# SmartIMU_Dev_Sch.net
KiCad netlist of a schematic drawn in Altium Designer
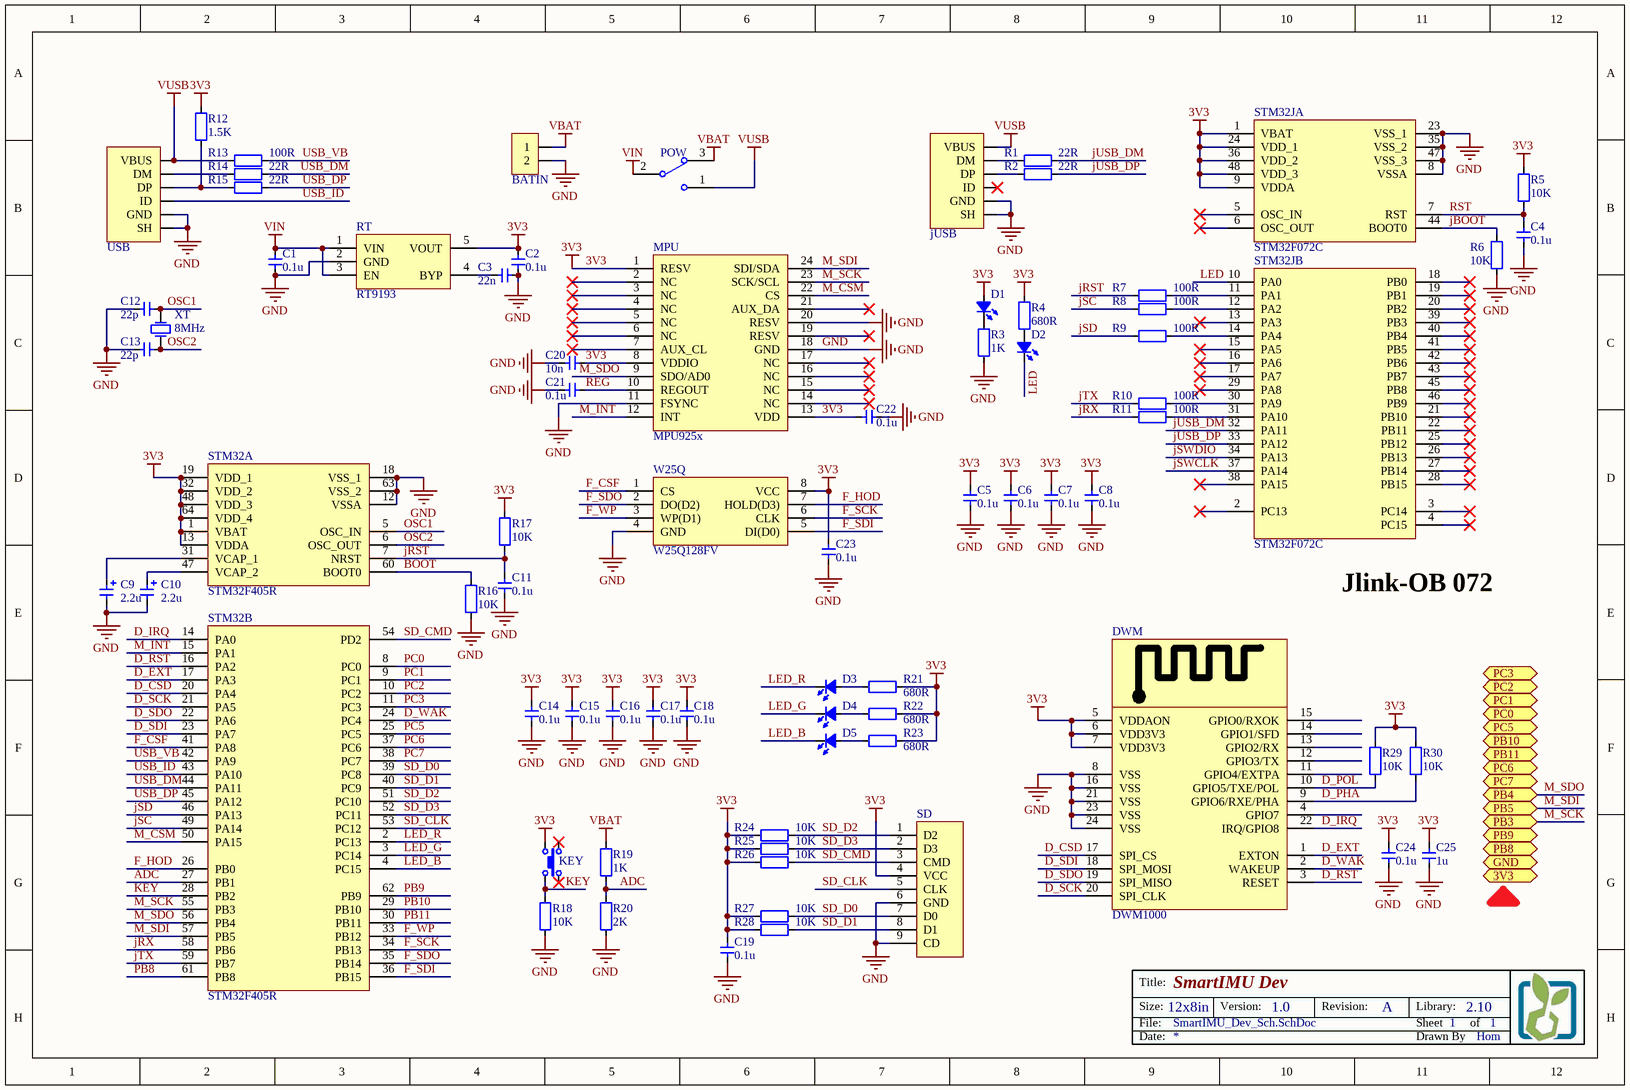
[diagram p0: SmartIMU_Dev_Sch.SchDoc]

(export (version "E")
  (design (tool "Eeschema 10.0.6"))
  (components
    (comp (ref "BATIN")
      (value "MX1.25_2P")
      (footprint "PCB_Connector:MX1.25_S90_2P")
      (description "MX")
      (libsource (lib "SCH_Connector") (part "MX1.25_2P"))
    )
    (comp (ref "C1")
      (value "0.1u")
      (footprint "PCB_PassiveCap:CAP_0603")
      (description "Capacitor")
      (fields (field (name "Comment") "Cap_0603"))
      (libsource (lib "SCH_Passive") (part "Cap_0603"))
    )
    (comp (ref "C2")
      (value "0.1u")
      (footprint "PCB_PassiveCap:CAP_0603")
      (description "Capacitor")
      (fields (field (name "Comment") "Cap_0603"))
      (libsource (lib "SCH_Passive") (part "Cap_0603"))
    )
    (comp (ref "C3")
      (value "22n")
      (footprint "PCB_PassiveCap:CAP_0603")
      (description "Capacitor")
      (fields (field (name "Comment") "Cap_0603"))
      (libsource (lib "SCH_Passive") (part "Cap_0603"))
    )
    (comp (ref "C4")
      (value "0.1u")
      (footprint "PCB_PassiveCap:CAP_0603")
      (description "Capacitor")
      (fields (field (name "Comment") "Cap_0603"))
      (libsource (lib "SCH_Passive") (part "Cap_0603"))
    )
    (comp (ref "C5")
      (value "0.1u")
      (footprint "PCB_PassiveCap:CAP_0603")
      (description "Capacitor")
      (fields (field (name "Comment") "Cap_0603"))
      (libsource (lib "SCH_Passive") (part "Cap_0603"))
    )
    (comp (ref "C6")
      (value "0.1u")
      (footprint "PCB_PassiveCap:CAP_0603")
      (description "Capacitor")
      (fields (field (name "Comment") "Cap_0603"))
      (libsource (lib "SCH_Passive") (part "Cap_0603"))
    )
    (comp (ref "C7")
      (value "0.1u")
      (footprint "PCB_PassiveCap:CAP_0603")
      (description "Capacitor")
      (fields (field (name "Comment") "Cap_0603"))
      (libsource (lib "SCH_Passive") (part "Cap_0603"))
    )
    (comp (ref "C8")
      (value "0.1u")
      (footprint "PCB_PassiveCap:CAP_0603")
      (description "Capacitor")
      (fields (field (name "Comment") "Cap_0603"))
      (libsource (lib "SCH_Passive") (part "Cap_0603"))
    )
    (comp (ref "C9")
      (value "2.2u")
      (footprint "PCB_PassiveCap:CAP_TAN_P0805")
      (description "Capacitor")
      (fields (field (name "Comment") "Cap_Tan_0805"))
      (libsource (lib "SCH_Passive") (part "Cap_Tan_0805"))
    )
    (comp (ref "C10")
      (value "2.2u")
      (footprint "PCB_PassiveCap:CAP_TAN_P0805")
      (description "Capacitor")
      (fields (field (name "Comment") "Cap_Tan_0805"))
      (libsource (lib "SCH_Passive") (part "Cap_Tan_0805"))
    )
    (comp (ref "C11")
      (value "0.1u")
      (footprint "PCB_PassiveCap:CAP_0603")
      (description "Capacitor")
      (fields (field (name "Comment") "Cap_0603"))
      (libsource (lib "SCH_Passive") (part "Cap_0603"))
    )
    (comp (ref "C12")
      (value "22p")
      (footprint "PCB_PassiveCap:CAP_0603")
      (description "Capacitor")
      (fields (field (name "Comment") "Cap_0603"))
      (libsource (lib "SCH_Passive") (part "Cap_0603"))
    )
    (comp (ref "C13")
      (value "22p")
      (footprint "PCB_PassiveCap:CAP_0603")
      (description "Capacitor")
      (fields (field (name "Comment") "Cap_0603"))
      (libsource (lib "SCH_Passive") (part "Cap_0603"))
    )
    (comp (ref "C14")
      (value "0.1u")
      (footprint "PCB_PassiveCap:CAP_0603")
      (description "Capacitor")
      (fields (field (name "Comment") "Cap_0603"))
      (libsource (lib "SCH_Passive") (part "Cap_0603"))
    )
    (comp (ref "C15")
      (value "0.1u")
      (footprint "PCB_PassiveCap:CAP_0603")
      (description "Capacitor")
      (fields (field (name "Comment") "Cap_0603"))
      (libsource (lib "SCH_Passive") (part "Cap_0603"))
    )
    (comp (ref "C16")
      (value "0.1u")
      (footprint "PCB_PassiveCap:CAP_0603")
      (description "Capacitor")
      (fields (field (name "Comment") "Cap_0603"))
      (libsource (lib "SCH_Passive") (part "Cap_0603"))
    )
    (comp (ref "C17")
      (value "0.1u")
      (footprint "PCB_PassiveCap:CAP_0603")
      (description "Capacitor")
      (fields (field (name "Comment") "Cap_0603"))
      (libsource (lib "SCH_Passive") (part "Cap_0603"))
    )
    (comp (ref "C18")
      (value "0.1u")
      (footprint "PCB_PassiveCap:CAP_0603")
      (description "Capacitor")
      (fields (field (name "Comment") "Cap_0603"))
      (libsource (lib "SCH_Passive") (part "Cap_0603"))
    )
    (comp (ref "C19")
      (value "0.1u")
      (footprint "PCB_PassiveCap:CAP_0603")
      (description "Capacitor")
      (fields (field (name "Comment") "Cap_0603"))
      (libsource (lib "SCH_Passive") (part "Cap_0603"))
    )
    (comp (ref "C20")
      (value "10n")
      (footprint "PCB_PassiveCap:CAP_0603")
      (description "Capacitor")
      (fields (field (name "Comment") "Cap_0603"))
      (libsource (lib "SCH_Passive") (part "Cap_0603"))
    )
    (comp (ref "C21")
      (value "0.1u")
      (footprint "PCB_PassiveCap:CAP_0603")
      (description "Capacitor")
      (fields (field (name "Comment") "Cap_0603"))
      (libsource (lib "SCH_Passive") (part "Cap_0603"))
    )
    (comp (ref "C22")
      (value "0.1u")
      (footprint "PCB_PassiveCap:CAP_0603")
      (description "Capacitor")
      (fields (field (name "Comment") "Cap_0603"))
      (libsource (lib "SCH_Passive") (part "Cap_0603"))
    )
    (comp (ref "C23")
      (value "0.1u")
      (footprint "PCB_PassiveCap:CAP_0603")
      (description "Capacitor")
      (fields (field (name "Comment") "Cap_0603"))
      (libsource (lib "SCH_Passive") (part "Cap_0603"))
    )
    (comp (ref "C24")
      (value "0.1u")
      (footprint "PCB_PassiveCap:CAP_0603")
      (description "Capacitor")
      (fields (field (name "Comment") "Cap_0603"))
      (libsource (lib "SCH_Passive") (part "Cap_0603"))
    )
    (comp (ref "C25")
      (value "1u")
      (footprint "PCB_PassiveCap:CAP_0603")
      (description "Capacitor")
      (fields (field (name "Comment") "Cap_0603"))
      (libsource (lib "SCH_Passive") (part "Cap_0603"))
    )
    (comp (ref "D1")
      (value "LED_0603")
      (footprint "PCB_ActiveLED:LED_0603_YELLOW")
      (description "LED")
      (libsource (lib "SCH_Active") (part "LED_0603"))
    )
    (comp (ref "D2")
      (value "LED_0603")
      (footprint "PCB_ActiveLED:LED_0603_ORANGE")
      (description "LED")
      (libsource (lib "SCH_Active") (part "LED_0603"))
    )
    (comp (ref "D3")
      (value "LED_0603")
      (footprint "PCB_ActiveLED:LED_0603_RED")
      (description "LED")
      (libsource (lib "SCH_Active") (part "LED_0603"))
    )
    (comp (ref "D4")
      (value "LED_0603")
      (footprint "PCB_ActiveLED:LED_0603_GREEN")
      (description "LED")
      (libsource (lib "SCH_Active") (part "LED_0603"))
    )
    (comp (ref "D5")
      (value "LED_0603")
      (footprint "PCB_ActiveLED:LED_0603_BLUE")
      (description "LED")
      (libsource (lib "SCH_Active") (part "LED_0603"))
    )
    (comp (ref "DWM")
      (value "DWM1000")
      (footprint "PCB_Module:DWM1000")
      (description "Module")
      (fields (field (name "MANUFACTURER") "Decawave Limited"))
      (libsource (lib "SCH_Module") (part "DWM1000"))
    )
    (comp (ref "jUSB")
      (value "USB_Micro")
      (footprint "PCB_USB:USB_Micro-AB")
      (description "USB")
      (libsource (lib "SCH_USB") (part "USB_Micro"))
    )
    (comp (ref "KEY")
      (value "ButtonTACT")
      (footprint "PCB_Switch:ButtonTACT_3.5*3.55_90")
      (description "Button")
      (libsource (lib "SCH_Switch") (part "ButtonTACT"))
    )
    (comp (ref "MPU")
      (value "MPU925x")
      (footprint "PCB_IntegratedCircuit:QFN_P0.4_24")
      (description "Sensor Motion")
      (libsource (lib "SCH_IntegratedCircuit") (part "MPU925x"))
    )
    (comp (ref "POW")
      (value "SwitchSPDT_2.8x6.6_90")
      (footprint "PCB_Switch:SwitchSPDT_2.8X6.6_90")
      (description "Switch")
      (libsource (lib "SCH_Switch") (part "SwitchSPDT_2.8x6.6_90"))
    )
    (comp (ref "R1")
      (value "22R")
      (footprint "PCB_PassiveRes:RES_0603")
      (description "Resistor")
      (fields (field (name "Comment") "Res_0603"))
      (libsource (lib "") (part "Res_0603_1"))
    )
    (comp (ref "R2")
      (value "22R")
      (footprint "PCB_PassiveRes:RES_0603")
      (description "Resistor")
      (fields (field (name "Comment") "Res_0603"))
      (libsource (lib "") (part "Res_0603_1"))
    )
    (comp (ref "R3")
      (value "1K")
      (footprint "PCB_PassiveRes:RES_0603")
      (description "Resistor")
      (fields (field (name "Comment") "Res_0603"))
      (libsource (lib "") (part "Res_0603_3"))
    )
    (comp (ref "R4")
      (value "680R")
      (footprint "PCB_PassiveRes:RES_0603")
      (description "Resistor")
      (fields (field (name "Comment") "Res_0603"))
      (libsource (lib "") (part "Res_0603_3"))
    )
    (comp (ref "R5")
      (value "10K")
      (footprint "PCB_PassiveRes:RES_0603")
      (description "Resistor")
      (fields (field (name "Comment") "Res_0603"))
      (libsource (lib "") (part "Res_0603_3"))
    )
    (comp (ref "R6")
      (value "10K")
      (footprint "PCB_PassiveRes:RES_0603")
      (description "Resistor")
      (fields (field (name "Comment") "Res_0603"))
      (libsource (lib "") (part "Res_0603_3"))
    )
    (comp (ref "R7")
      (value "100R")
      (footprint "PCB_PassiveRes:RES_0603")
      (description "Resistor")
      (fields (field (name "Comment") "Res_0603"))
      (libsource (lib "") (part "Res_0603_1"))
    )
    (comp (ref "R8")
      (value "100R")
      (footprint "PCB_PassiveRes:RES_0603")
      (description "Resistor")
      (fields (field (name "Comment") "Res_0603"))
      (libsource (lib "") (part "Res_0603_1"))
    )
    (comp (ref "R9")
      (value "100R")
      (footprint "PCB_PassiveRes:RES_0603")
      (description "Resistor")
      (fields (field (name "Comment") "Res_0603"))
      (libsource (lib "") (part "Res_0603_1"))
    )
    (comp (ref "R10")
      (value "100R")
      (footprint "PCB_PassiveRes:RES_0603")
      (description "Resistor")
      (fields (field (name "Comment") "Res_0603"))
      (libsource (lib "") (part "Res_0603_1"))
    )
    (comp (ref "R11")
      (value "100R")
      (footprint "PCB_PassiveRes:RES_0603")
      (description "Resistor")
      (fields (field (name "Comment") "Res_0603"))
      (libsource (lib "") (part "Res_0603_1"))
    )
    (comp (ref "R12")
      (value "1.5K")
      (footprint "PCB_PassiveRes:RES_0603")
      (description "Resistor")
      (fields (field (name "Comment") "Res_0603"))
      (libsource (lib "") (part "Res_0603_2"))
    )
    (comp (ref "R13")
      (value "100R")
      (footprint "PCB_PassiveRes:RES_0603")
      (description "Resistor")
      (fields (field (name "Comment") "Res_0603"))
      (libsource (lib "SCH_Passive") (part "Res_0603"))
    )
    (comp (ref "R14")
      (value "22R")
      (footprint "PCB_PassiveRes:RES_0603")
      (description "Resistor")
      (fields (field (name "Comment") "Res_0603"))
      (libsource (lib "SCH_Passive") (part "Res_0603"))
    )
    (comp (ref "R15")
      (value "22R")
      (footprint "PCB_PassiveRes:RES_0603")
      (description "Resistor")
      (fields (field (name "Comment") "Res_0603"))
      (libsource (lib "SCH_Passive") (part "Res_0603"))
    )
    (comp (ref "R16")
      (value "10K")
      (footprint "PCB_PassiveRes:RES_0603")
      (description "Resistor")
      (fields (field (name "Comment") "Res_0603"))
      (libsource (lib "") (part "Res_0603_3"))
    )
    (comp (ref "R17")
      (value "10K")
      (footprint "PCB_PassiveRes:RES_0603")
      (description "Resistor")
      (fields (field (name "Comment") "Res_0603"))
      (libsource (lib "") (part "Res_0603_3"))
    )
    (comp (ref "R18")
      (value "10K")
      (footprint "PCB_PassiveRes:RES_0603")
      (description "Resistor")
      (fields (field (name "Comment") "Res_0603"))
      (libsource (lib "") (part "Res_0603_3"))
    )
    (comp (ref "R19")
      (value "1K")
      (footprint "PCB_PassiveRes:RES_0603")
      (description "Resistor")
      (fields (field (name "Comment") "Res_0603"))
      (libsource (lib "") (part "Res_0603_2"))
    )
    (comp (ref "R20")
      (value "2K")
      (footprint "PCB_PassiveRes:RES_0603")
      (description "Resistor")
      (fields (field (name "Comment") "Res_0603"))
      (libsource (lib "") (part "Res_0603_2"))
    )
    (comp (ref "R21")
      (value "680R")
      (footprint "PCB_PassiveRes:RES_0603")
      (description "Resistor")
      (fields (field (name "Comment") "Res_0603"))
      (libsource (lib "SCH_Passive") (part "Res_0603"))
    )
    (comp (ref "R22")
      (value "680R")
      (footprint "PCB_PassiveRes:RES_0603")
      (description "Resistor")
      (fields (field (name "Comment") "Res_0603"))
      (libsource (lib "SCH_Passive") (part "Res_0603"))
    )
    (comp (ref "R23")
      (value "680R")
      (footprint "PCB_PassiveRes:RES_0603")
      (description "Resistor")
      (fields (field (name "Comment") "Res_0603"))
      (libsource (lib "SCH_Passive") (part "Res_0603"))
    )
    (comp (ref "R24")
      (value "10K")
      (footprint "PCB_PassiveRes:RES_0603")
      (description "Resistor")
      (fields (field (name "Comment") "Res_0603"))
      (libsource (lib "SCH_Passive") (part "Res_0603"))
    )
    (comp (ref "R25")
      (value "10K")
      (footprint "PCB_PassiveRes:RES_0603")
      (description "Resistor")
      (fields (field (name "Comment") "Res_0603"))
      (libsource (lib "SCH_Passive") (part "Res_0603"))
    )
    (comp (ref "R26")
      (value "10K")
      (footprint "PCB_PassiveRes:RES_0603")
      (description "Resistor")
      (fields (field (name "Comment") "Res_0603"))
      (libsource (lib "SCH_Passive") (part "Res_0603"))
    )
    (comp (ref "R27")
      (value "10K")
      (footprint "PCB_PassiveRes:RES_0603")
      (description "Resistor")
      (fields (field (name "Comment") "Res_0603"))
      (libsource (lib "SCH_Passive") (part "Res_0603"))
    )
    (comp (ref "R28")
      (value "10K")
      (footprint "PCB_PassiveRes:RES_0603")
      (description "Resistor")
      (fields (field (name "Comment") "Res_0603"))
      (libsource (lib "SCH_Passive") (part "Res_0603"))
    )
    (comp (ref "R29")
      (value "10K")
      (footprint "PCB_PassiveRes:RES_0603")
      (description "Resistor")
      (fields (field (name "Comment") "Res_0603"))
      (libsource (lib "") (part "Res_0603_3"))
    )
    (comp (ref "R30")
      (value "10K")
      (footprint "PCB_PassiveRes:RES_0603")
      (description "Resistor")
      (fields (field (name "Comment") "Res_0603"))
      (libsource (lib "") (part "Res_0603_3"))
    )
    (comp (ref "RT")
      (value "RT9193")
      (footprint "PCB_IntegratedCircuit:SOT23-5")
      (description "Power")
      (libsource (lib "SCH_IntegratedCircuit") (part "RT9193"))
    )
    (comp (ref "SD")
      (value "SD_Card_TF")
      (footprint "PCB_SDCard:SD_Card_TF")
      (description "SD")
      (libsource (lib "SCH_SDCard") (part "SD_Card_TF"))
    )
    (comp (ref "STM32")
      (value "STM32F405R")
      (footprint "PCB_IntegratedCircuit:LQFP_P0.5_64")
      (description "MCU")
      (libsource (lib "SCH_IntegratedCircuit") (part "STM32F405R"))
    )
    (comp (ref "STM32J")
      (value "STM32F072C")
      (footprint "PCB_IntegratedCircuit:LQFP_P0.5_48")
      (description "MCU")
      (libsource (lib "SCH_IntegratedCircuit") (part "STM32F103C"))
    )
    (comp (ref "USB")
      (value "USB_Micro")
      (footprint "PCB_USB:USB_Micro-AB")
      (description "USB")
      (libsource (lib "SCH_USB") (part "USB_Micro"))
    )
    (comp (ref "W25Q")
      (value "W25Q128FV")
      (footprint "PCB_IntegratedCircuit:SON_P1.27H_8")
      (description "FLASH")
      (libsource (lib "SCH_IntegratedCircuit") (part "W25Q_8"))
    )
    (comp (ref "XT")
      (value "8MHz")
      (footprint "PCB_Oscillator:XT_5032_2")
      (description "Crystal Oscillator")
      (fields (field (name "Comment") "XTAL_5032_2P"))
      (libsource (lib "SCH_Oscillator") (part "XTAL_5032_2P"))
    )
  )
  (nets
    (net (code "1") (name "/ADC") (class "Default")
      (node (ref "R19") (pin "2") (pinfunction "2_2") (pintype "passive"))
      (node (ref "R20") (pin "1") (pinfunction "1_1") (pintype "passive"))
      (node (ref "STM32") (pin "27") (pinfunction "PB1_27") (pintype "passive"))
    )
    (net (code "2") (name "/BOOT") (class "Default")
      (node (ref "R16") (pin "2") (pinfunction "2_2") (pintype "passive"))
      (node (ref "STM32") (pin "60") (pinfunction "BOOT0_60") (pintype "passive"))
    )
    (net (code "3") (name "/D_CSD") (class "Default")
      (node (ref "DWM") (pin "17") (pinfunction "SPI_CS_17") (pintype "passive"))
      (node (ref "STM32") (pin "20") (pinfunction "PA4_20") (pintype "passive"))
    )
    (net (code "4") (name "/D_EXT") (class "Default")
      (node (ref "DWM") (pin "1") (pinfunction "EXTON_1") (pintype "passive"))
      (node (ref "STM32") (pin "17") (pinfunction "PA3_17") (pintype "passive"))
    )
    (net (code "5") (name "/D_IRQ") (class "Default")
      (node (ref "DWM") (pin "22") (pinfunction "IRQ/GPIO8_22") (pintype "passive"))
      (node (ref "STM32") (pin "14") (pinfunction "PA0_14") (pintype "passive"))
    )
    (net (code "6") (name "/D_PHA") (class "Default")
      (node (ref "DWM") (pin "9") (pinfunction "GPIO6/RXE/PHA_9") (pintype "passive"))
      (node (ref "R30") (pin "1") (pinfunction "1_1") (pintype "passive"))
    )
    (net (code "7") (name "/D_POL") (class "Default")
      (node (ref "DWM") (pin "10") (pinfunction "GPIO5/TXE/POL_10") (pintype "passive"))
      (node (ref "R29") (pin "1") (pinfunction "1_1") (pintype "passive"))
    )
    (net (code "8") (name "/D_RST") (class "Default")
      (node (ref "DWM") (pin "3") (pinfunction "RESET_3") (pintype "passive"))
      (node (ref "STM32") (pin "16") (pinfunction "PA2_16") (pintype "passive"))
    )
    (net (code "9") (name "/D_SCK") (class "Default")
      (node (ref "DWM") (pin "20") (pinfunction "SPI_CLK_20") (pintype "passive"))
      (node (ref "STM32") (pin "21") (pinfunction "PA5_21") (pintype "passive"))
    )
    (net (code "10") (name "/D_SDI") (class "Default")
      (node (ref "DWM") (pin "18") (pinfunction "SPI_MOSI_18") (pintype "passive"))
      (node (ref "STM32") (pin "23") (pinfunction "PA7_23") (pintype "passive"))
    )
    (net (code "11") (name "/D_SDO") (class "Default")
      (node (ref "DWM") (pin "19") (pinfunction "SPI_MISO_19") (pintype "passive"))
      (node (ref "STM32") (pin "22") (pinfunction "PA6_22") (pintype "passive"))
    )
    (net (code "12") (name "/D_WAK") (class "Default")
      (node (ref "DWM") (pin "2") (pinfunction "WAKEUP_2") (pintype "passive"))
      (node (ref "STM32") (pin "24") (pinfunction "PC4_24") (pintype "passive"))
    )
    (net (code "13") (name "/F_CSF") (class "Default")
      (node (ref "STM32") (pin "41") (pinfunction "PA8_41") (pintype "passive"))
      (node (ref "W25Q") (pin "1") (pinfunction "CS_1") (pintype "passive"))
    )
    (net (code "14") (name "/F_HOD") (class "Default")
      (node (ref "STM32") (pin "26") (pinfunction "PB0_26") (pintype "passive"))
      (node (ref "W25Q") (pin "7") (pinfunction "HOLD(D3)_7") (pintype "passive"))
    )
    (net (code "15") (name "/F_SCK") (class "Default")
      (node (ref "STM32") (pin "34") (pinfunction "PB13_34") (pintype "passive"))
      (node (ref "W25Q") (pin "6") (pinfunction "CLK_6") (pintype "passive"))
    )
    (net (code "16") (name "/F_SDI") (class "Default")
      (node (ref "STM32") (pin "36") (pinfunction "PB15_36") (pintype "passive"))
      (node (ref "W25Q") (pin "5") (pinfunction "DI(D0)_5") (pintype "passive"))
    )
    (net (code "17") (name "/F_SDO") (class "Default")
      (node (ref "STM32") (pin "35") (pinfunction "PB14_35") (pintype "passive"))
      (node (ref "W25Q") (pin "2") (pinfunction "DO(D2)_2") (pintype "passive"))
    )
    (net (code "18") (name "/F_WP") (class "Default")
      (node (ref "STM32") (pin "33") (pinfunction "PB12_33") (pintype "passive"))
      (node (ref "W25Q") (pin "3") (pinfunction "WP(D1)_3") (pintype "passive"))
    )
    (net (code "19") (name "/KEY") (class "Default")
      (node (ref "KEY") (pin "1") (pinfunction "1_1") (pintype "passive"))
      (node (ref "R18") (pin "2") (pinfunction "2_2") (pintype "passive"))
      (node (ref "STM32") (pin "28") (pinfunction "PB2_28") (pintype "passive"))
    )
    (net (code "20") (name "/LED") (class "Default")
      (node (ref "D2") (pin "2") (pinfunction "K_2") (pintype "passive"))
      (node (ref "STM32J") (pin "10") (pinfunction "PA0_10") (pintype "passive"))
    )
    (net (code "21") (name "/LED_B") (class "Default")
      (node (ref "D5") (pin "2") (pinfunction "K_2") (pintype "passive"))
      (node (ref "STM32") (pin "4") (pinfunction "PC15_4") (pintype "passive"))
    )
    (net (code "22") (name "/LED_G") (class "Default")
      (node (ref "D4") (pin "2") (pinfunction "K_2") (pintype "passive"))
      (node (ref "STM32") (pin "3") (pinfunction "PC14_3") (pintype "passive"))
    )
    (net (code "23") (name "/LED_R") (class "Default")
      (node (ref "D3") (pin "2") (pinfunction "K_2") (pintype "passive"))
      (node (ref "STM32") (pin "2") (pinfunction "PC13_2") (pintype "passive"))
    )
    (net (code "24") (name "/M_CSM") (class "Default")
      (node (ref "MPU") (pin "22") (pinfunction "CS_22") (pintype "passive"))
      (node (ref "STM32") (pin "50") (pinfunction "PA15_50") (pintype "passive"))
    )
    (net (code "25") (name "/M_INT") (class "Default")
      (node (ref "MPU") (pin "12") (pinfunction "INT_12") (pintype "passive"))
      (node (ref "STM32") (pin "15") (pinfunction "PA1_15") (pintype "passive"))
    )
    (net (code "26") (name "/M_SCK") (class "Default")
      (node (ref "MPU") (pin "23") (pinfunction "SCK/SCL_23") (pintype "passive"))
      (node (ref "STM32") (pin "55") (pinfunction "PB3_55") (pintype "passive"))
    )
    (net (code "27") (name "/M_SDI") (class "Default")
      (node (ref "MPU") (pin "24") (pinfunction "SDI/SDA_24") (pintype "passive"))
      (node (ref "STM32") (pin "57") (pinfunction "PB5_57") (pintype "passive"))
    )
    (net (code "28") (name "/M_SDO") (class "Default")
      (node (ref "MPU") (pin "9") (pinfunction "SDO/AD0_9") (pintype "passive"))
      (node (ref "STM32") (pin "56") (pinfunction "PB4_56") (pintype "passive"))
    )
    (net (code "29") (name "/OSC1") (class "Default")
      (node (ref "C12") (pin "1") (pinfunction "1_1") (pintype "passive"))
      (node (ref "STM32") (pin "5") (pinfunction "OSC_IN_5") (pintype "passive"))
      (node (ref "XT") (pin "2") (pinfunction "OSC2_2") (pintype "passive"))
    )
    (net (code "30") (name "/OSC2") (class "Default")
      (node (ref "C13") (pin "1") (pinfunction "1_1") (pintype "passive"))
      (node (ref "STM32") (pin "6") (pinfunction "OSC_OUT_6") (pintype "passive"))
      (node (ref "XT") (pin "1") (pinfunction "OSC1_1") (pintype "passive"))
    )
    (net (code "31") (name "/PB8") (class "Default")
      (node (ref "STM32") (pin "61") (pinfunction "PB8_61") (pintype "passive"))
    )
    (net (code "32") (name "/PB9") (class "Default")
      (node (ref "STM32") (pin "62") (pinfunction "PB9_62") (pintype "passive"))
    )
    (net (code "33") (name "/PB10") (class "Default")
      (node (ref "STM32") (pin "29") (pinfunction "PB10_29") (pintype "passive"))
    )
    (net (code "34") (name "/PB11") (class "Default")
      (node (ref "STM32") (pin "30") (pinfunction "PB11_30") (pintype "passive"))
    )
    (net (code "35") (name "/PC0") (class "Default")
      (node (ref "STM32") (pin "8") (pinfunction "PC0_8") (pintype "passive"))
    )
    (net (code "36") (name "/PC1") (class "Default")
      (node (ref "STM32") (pin "9") (pinfunction "PC1_9") (pintype "passive"))
    )
    (net (code "37") (name "/PC2") (class "Default")
      (node (ref "STM32") (pin "10") (pinfunction "PC2_10") (pintype "passive"))
    )
    (net (code "38") (name "/PC3") (class "Default")
      (node (ref "STM32") (pin "11") (pinfunction "PC3_11") (pintype "passive"))
    )
    (net (code "39") (name "/PC5") (class "Default")
      (node (ref "STM32") (pin "25") (pinfunction "PC5_25") (pintype "passive"))
    )
    (net (code "40") (name "/PC6") (class "Default")
      (node (ref "STM32") (pin "37") (pinfunction "PC6_37") (pintype "passive"))
    )
    (net (code "41") (name "/PC7") (class "Default")
      (node (ref "STM32") (pin "38") (pinfunction "PC7_38") (pintype "passive"))
    )
    (net (code "42") (name "/REG") (class "Default")
      (node (ref "C21") (pin "2") (pinfunction "2_2") (pintype "passive"))
      (node (ref "MPU") (pin "10") (pinfunction "REGOUT_10") (pintype "passive"))
    )
    (net (code "43") (name "/RST") (class "Default")
      (node (ref "C4") (pin "2") (pinfunction "2_2") (pintype "passive"))
      (node (ref "R5") (pin "1") (pinfunction "1_1") (pintype "passive"))
      (node (ref "STM32J") (pin "7") (pinfunction "RST_7") (pintype "passive"))
    )
    (net (code "44") (name "/SD_CLK") (class "Default")
      (node (ref "SD") (pin "5") (pinfunction "CLK_5") (pintype "passive"))
      (node (ref "STM32") (pin "53") (pinfunction "PC12_53") (pintype "passive"))
    )
    (net (code "45") (name "/SD_CMD") (class "Default")
      (node (ref "R26") (pin "1") (pinfunction "1_1") (pintype "passive"))
      (node (ref "SD") (pin "3") (pinfunction "CMD_3") (pintype "passive"))
      (node (ref "STM32") (pin "54") (pinfunction "PD2_54") (pintype "passive"))
    )
    (net (code "46") (name "/SD_D0") (class "Default")
      (node (ref "R27") (pin "1") (pinfunction "1_1") (pintype "passive"))
      (node (ref "SD") (pin "7") (pinfunction "D0_7") (pintype "passive"))
      (node (ref "STM32") (pin "39") (pinfunction "PC8_39") (pintype "passive"))
    )
    (net (code "47") (name "/SD_D1") (class "Default")
      (node (ref "R28") (pin "1") (pinfunction "1_1") (pintype "passive"))
      (node (ref "SD") (pin "8") (pinfunction "D1_8") (pintype "passive"))
      (node (ref "STM32") (pin "40") (pinfunction "PC9_40") (pintype "passive"))
    )
    (net (code "48") (name "/SD_D2") (class "Default")
      (node (ref "R24") (pin "1") (pinfunction "1_1") (pintype "passive"))
      (node (ref "SD") (pin "1") (pinfunction "D2_1") (pintype "passive"))
      (node (ref "STM32") (pin "51") (pinfunction "PC10_51") (pintype "passive"))
    )
    (net (code "49") (name "/SD_D3") (class "Default")
      (node (ref "R25") (pin "1") (pinfunction "1_1") (pintype "passive"))
      (node (ref "SD") (pin "2") (pinfunction "D3_2") (pintype "passive"))
      (node (ref "STM32") (pin "52") (pinfunction "PC11_52") (pintype "passive"))
    )
    (net (code "50") (name "/USB_DM") (class "Default")
      (node (ref "R14") (pin "1") (pinfunction "1_1") (pintype "passive"))
      (node (ref "STM32") (pin "44") (pinfunction "PA11_44") (pintype "passive"))
    )
    (net (code "51") (name "/USB_DP") (class "Default")
      (node (ref "R15") (pin "1") (pinfunction "1_1") (pintype "passive"))
      (node (ref "STM32") (pin "45") (pinfunction "PA12_45") (pintype "passive"))
    )
    (net (code "52") (name "/USB_ID") (class "Default")
      (node (ref "STM32") (pin "43") (pinfunction "PA10_43") (pintype "passive"))
      (node (ref "USB") (pin "4") (pinfunction "ID_4") (pintype "passive"))
    )
    (net (code "53") (name "/USB_VB") (class "Default")
      (node (ref "R13") (pin "1") (pinfunction "1_1") (pintype "passive"))
      (node (ref "STM32") (pin "42") (pinfunction "PA9_42") (pintype "passive"))
    )
    (net (code "54") (name "/jBOOT") (class "Default")
      (node (ref "R6") (pin "2") (pinfunction "2_2") (pintype "passive"))
      (node (ref "STM32J") (pin "44") (pinfunction "BOOT0_44") (pintype "passive"))
    )
    (net (code "55") (name "/jRST") (class "Default")
      (node (ref "C11") (pin "2") (pinfunction "2_2") (pintype "passive"))
      (node (ref "R17") (pin "1") (pinfunction "1_1") (pintype "passive"))
      (node (ref "R7") (pin "1") (pinfunction "1_1") (pintype "passive"))
      (node (ref "STM32") (pin "7") (pinfunction "NRST_7") (pintype "passive"))
    )
    (net (code "56") (name "/jRX") (class "Default")
      (node (ref "R11") (pin "1") (pinfunction "1_1") (pintype "passive"))
      (node (ref "STM32") (pin "58") (pinfunction "PB6_58") (pintype "passive"))
    )
    (net (code "57") (name "/jSC") (class "Default")
      (node (ref "R8") (pin "1") (pinfunction "1_1") (pintype "passive"))
      (node (ref "STM32") (pin "49") (pinfunction "PA14_49") (pintype "passive"))
    )
    (net (code "58") (name "/jSD") (class "Default")
      (node (ref "R9") (pin "1") (pinfunction "1_1") (pintype "passive"))
      (node (ref "STM32") (pin "46") (pinfunction "PA13_46") (pintype "passive"))
    )
    (net (code "59") (name "/jSWCLK") (class "Default")
      (node (ref "STM32J") (pin "37") (pinfunction "PA14_37") (pintype "passive"))
    )
    (net (code "60") (name "/jSWDIO") (class "Default")
      (node (ref "STM32J") (pin "34") (pinfunction "PA13_34") (pintype "passive"))
    )
    (net (code "61") (name "/jTX") (class "Default")
      (node (ref "R10") (pin "1") (pinfunction "1_1") (pintype "passive"))
      (node (ref "STM32") (pin "59") (pinfunction "PB7_59") (pintype "passive"))
    )
    (net (code "62") (name "/jUSB_DM") (class "Default")
      (node (ref "R1") (pin "2") (pinfunction "2_2") (pintype "passive"))
      (node (ref "STM32J") (pin "32") (pinfunction "PA11_32") (pintype "passive"))
    )
    (net (code "63") (name "/jUSB_DP") (class "Default")
      (node (ref "R2") (pin "2") (pinfunction "2_2") (pintype "passive"))
      (node (ref "STM32J") (pin "33") (pinfunction "PA12_33") (pintype "passive"))
    )
    (net (code "64") (name "3V3") (class "Default")
      (node (ref "C14") (pin "1") (pinfunction "1_1") (pintype "passive"))
      (node (ref "C15") (pin "1") (pinfunction "1_1") (pintype "passive"))
      (node (ref "C16") (pin "1") (pinfunction "1_1") (pintype "passive"))
      (node (ref "C17") (pin "1") (pinfunction "1_1") (pintype "passive"))
      (node (ref "C18") (pin "2") (pinfunction "2_2") (pintype "passive"))
      (node (ref "C19") (pin "1") (pinfunction "1_1") (pintype "passive"))
      (node (ref "C2") (pin "2") (pinfunction "2_2") (pintype "passive"))
      (node (ref "C20") (pin "2") (pinfunction "2_2") (pintype "passive"))
      (node (ref "C22") (pin "2") (pinfunction "2_2") (pintype "passive"))
      (node (ref "C23") (pin "1") (pinfunction "1_1") (pintype "passive"))
      (node (ref "C24") (pin "1") (pinfunction "1_1") (pintype "passive"))
      (node (ref "C25") (pin "1") (pinfunction "1_1") (pintype "passive"))
      (node (ref "C5") (pin "2") (pinfunction "2_2") (pintype "passive"))
      (node (ref "C6") (pin "2") (pinfunction "2_2") (pintype "passive"))
      (node (ref "C7") (pin "2") (pinfunction "2_2") (pintype "passive"))
      (node (ref "C8") (pin "2") (pinfunction "2_2") (pintype "passive"))
      (node (ref "D1") (pin "1") (pinfunction "A_1") (pintype "passive"))
      (node (ref "DWM") (pin "5") (pinfunction "VDDAON_5") (pintype "passive"))
      (node (ref "DWM") (pin "6") (pinfunction "VDD3V3_6") (pintype "passive"))
      (node (ref "DWM") (pin "7") (pinfunction "VDD3V3_7") (pintype "passive"))
      (node (ref "KEY") (pin "2") (pinfunction "2_2") (pintype "passive"))
      (node (ref "MPU") (pin "1") (pinfunction "RESV_1") (pintype "passive"))
      (node (ref "MPU") (pin "13") (pinfunction "VDD_13") (pintype "passive"))
      (node (ref "MPU") (pin "8") (pinfunction "VDDIO_8") (pintype "passive"))
      (node (ref "R12") (pin "1") (pinfunction "1_1") (pintype "passive"))
      (node (ref "R17") (pin "2") (pinfunction "2_2") (pintype "passive"))
      (node (ref "R21") (pin "1") (pinfunction "1_1") (pintype "passive"))
      (node (ref "R22") (pin "1") (pinfunction "1_1") (pintype "passive"))
      (node (ref "R23") (pin "1") (pinfunction "1_1") (pintype "passive"))
      (node (ref "R24") (pin "2") (pinfunction "2_2") (pintype "passive"))
      (node (ref "R25") (pin "2") (pinfunction "2_2") (pintype "passive"))
      (node (ref "R26") (pin "2") (pinfunction "2_2") (pintype "passive"))
      (node (ref "R27") (pin "2") (pinfunction "2_2") (pintype "passive"))
      (node (ref "R28") (pin "2") (pinfunction "2_2") (pintype "passive"))
      (node (ref "R29") (pin "2") (pinfunction "2_2") (pintype "passive"))
      (node (ref "R30") (pin "2") (pinfunction "2_2") (pintype "passive"))
      (node (ref "R4") (pin "2") (pinfunction "2_2") (pintype "passive"))
      (node (ref "R5") (pin "2") (pinfunction "2_2") (pintype "passive"))
      (node (ref "RT") (pin "5") (pinfunction "VOUT_5") (pintype "passive"))
      (node (ref "SD") (pin "4") (pinfunction "VCC_4") (pintype "passive"))
      (node (ref "STM32") (pin "1") (pinfunction "VBAT_1") (pintype "passive"))
      (node (ref "STM32") (pin "13") (pinfunction "VDDA_13") (pintype "passive"))
      (node (ref "STM32") (pin "19") (pinfunction "VDD_1_19") (pintype "passive"))
      (node (ref "STM32") (pin "32") (pinfunction "VDD_2_32") (pintype "passive"))
      (node (ref "STM32") (pin "48") (pinfunction "VDD_3_48") (pintype "passive"))
      (node (ref "STM32") (pin "64") (pinfunction "VDD_4_64") (pintype "passive"))
      (node (ref "STM32J") (pin "1") (pinfunction "VBAT_1") (pintype "passive"))
      (node (ref "STM32J") (pin "24") (pinfunction "VDD_1_24") (pintype "passive"))
      (node (ref "STM32J") (pin "36") (pinfunction "VDD_2_36") (pintype "passive"))
      (node (ref "STM32J") (pin "48") (pinfunction "VDD_3_48") (pintype "passive"))
      (node (ref "STM32J") (pin "9") (pinfunction "VDDA_9") (pintype "passive"))
      (node (ref "W25Q") (pin "8") (pinfunction "VCC_8") (pintype "passive"))
    )
    (net (code "65") (name "GND") (class "Default")
      (node (ref "BATIN") (pin "2") (pinfunction "2_2") (pintype "passive"))
      (node (ref "C1") (pin "1") (pinfunction "1_1") (pintype "passive"))
      (node (ref "C10") (pin "2") (pinfunction "2_2") (pintype "passive"))
      (node (ref "C11") (pin "1") (pinfunction "1_1") (pintype "passive"))
      (node (ref "C12") (pin "2") (pinfunction "2_2") (pintype "passive"))
      (node (ref "C13") (pin "2") (pinfunction "2_2") (pintype "passive"))
      (node (ref "C14") (pin "2") (pinfunction "2_2") (pintype "passive"))
      (node (ref "C15") (pin "2") (pinfunction "2_2") (pintype "passive"))
      (node (ref "C16") (pin "2") (pinfunction "2_2") (pintype "passive"))
      (node (ref "C17") (pin "2") (pinfunction "2_2") (pintype "passive"))
      (node (ref "C18") (pin "1") (pinfunction "1_1") (pintype "passive"))
      (node (ref "C19") (pin "2") (pinfunction "2_2") (pintype "passive"))
      (node (ref "C2") (pin "1") (pinfunction "1_1") (pintype "passive"))
      (node (ref "C20") (pin "1") (pinfunction "1_1") (pintype "passive"))
      (node (ref "C21") (pin "1") (pinfunction "1_1") (pintype "passive"))
      (node (ref "C22") (pin "1") (pinfunction "1_1") (pintype "passive"))
      (node (ref "C23") (pin "2") (pinfunction "2_2") (pintype "passive"))
      (node (ref "C24") (pin "2") (pinfunction "2_2") (pintype "passive"))
      (node (ref "C25") (pin "2") (pinfunction "2_2") (pintype "passive"))
      (node (ref "C3") (pin "1") (pinfunction "1_1") (pintype "passive"))
      (node (ref "C4") (pin "1") (pinfunction "1_1") (pintype "passive"))
      (node (ref "C5") (pin "1") (pinfunction "1_1") (pintype "passive"))
      (node (ref "C6") (pin "1") (pinfunction "1_1") (pintype "passive"))
      (node (ref "C7") (pin "1") (pinfunction "1_1") (pintype "passive"))
      (node (ref "C8") (pin "1") (pinfunction "1_1") (pintype "passive"))
      (node (ref "C9") (pin "2") (pinfunction "2_2") (pintype "passive"))
      (node (ref "DWM") (pin "16") (pinfunction "VSS_16") (pintype "passive"))
      (node (ref "DWM") (pin "21") (pinfunction "VSS_21") (pintype "passive"))
      (node (ref "DWM") (pin "23") (pinfunction "VSS_23") (pintype "passive"))
      (node (ref "DWM") (pin "24") (pinfunction "VSS_24") (pintype "passive"))
      (node (ref "DWM") (pin "8") (pinfunction "VSS_8") (pintype "passive"))
      (node (ref "MPU") (pin "11") (pinfunction "FSYNC_11") (pintype "passive"))
      (node (ref "MPU") (pin "18") (pinfunction "GND_18") (pintype "passive"))
      (node (ref "MPU") (pin "20") (pinfunction "RESV_20") (pintype "passive"))
      (node (ref "R16") (pin "1") (pinfunction "1_1") (pintype "passive"))
      (node (ref "R18") (pin "1") (pinfunction "1_1") (pintype "passive"))
      (node (ref "R20") (pin "2") (pinfunction "2_2") (pintype "passive"))
      (node (ref "R3") (pin "1") (pinfunction "1_1") (pintype "passive"))
      (node (ref "R6") (pin "1") (pinfunction "1_1") (pintype "passive"))
      (node (ref "RT") (pin "2") (pinfunction "GND_2") (pintype "passive"))
      (node (ref "SD") (pin "6") (pinfunction "GND_6") (pintype "passive"))
      (node (ref "SD") (pin "9") (pinfunction "CD_9") (pintype "passive"))
      (node (ref "STM32") (pin "12") (pinfunction "VSSA_12") (pintype "passive"))
      (node (ref "STM32") (pin "18") (pinfunction "VSS_1_18") (pintype "passive"))
      (node (ref "STM32") (pin "63") (pinfunction "VSS_2_63") (pintype "passive"))
      (node (ref "STM32J") (pin "23") (pinfunction "VSS_1_23") (pintype "passive"))
      (node (ref "STM32J") (pin "35") (pinfunction "VSS_2_35") (pintype "passive"))
      (node (ref "STM32J") (pin "47") (pinfunction "VSS_3_47") (pintype "passive"))
      (node (ref "STM32J") (pin "8") (pinfunction "VSSA_8") (pintype "passive"))
      (node (ref "USB") (pin "0") (pinfunction "SH_0") (pintype "passive"))
      (node (ref "USB") (pin "5") (pinfunction "GND_5") (pintype "passive"))
      (node (ref "W25Q") (pin "4") (pinfunction "GND_4") (pintype "passive"))
      (node (ref "jUSB") (pin "0") (pinfunction "SH_0") (pintype "passive"))
      (node (ref "jUSB") (pin "5") (pinfunction "GND_5") (pintype "passive"))
    )
    (net (code "66") (name "Net-(D1-K)") (class "Default")
      (node (ref "D1") (pin "2") (pinfunction "K_2") (pintype "passive"))
      (node (ref "R3") (pin "2") (pinfunction "2_2") (pintype "passive"))
    )
    (net (code "67") (name "Net-(D2-A)") (class "Default")
      (node (ref "D2") (pin "1") (pinfunction "A_1") (pintype "passive"))
      (node (ref "R4") (pin "1") (pinfunction "1_1") (pintype "passive"))
    )
    (net (code "68") (name "Net-(D3-A)") (class "Default")
      (node (ref "D3") (pin "1") (pinfunction "A_1") (pintype "passive"))
      (node (ref "R21") (pin "2") (pinfunction "2_2") (pintype "passive"))
    )
    (net (code "69") (name "Net-(D4-A)") (class "Default")
      (node (ref "D4") (pin "1") (pinfunction "A_1") (pintype "passive"))
      (node (ref "R22") (pin "2") (pinfunction "2_2") (pintype "passive"))
    )
    (net (code "70") (name "Net-(D5-A)") (class "Default")
      (node (ref "D5") (pin "1") (pinfunction "A_1") (pintype "passive"))
      (node (ref "R23") (pin "2") (pinfunction "2_2") (pintype "passive"))
    )
    (net (code "71") (name "Net-(RT-BYP)") (class "Default")
      (node (ref "C3") (pin "2") (pinfunction "2_2") (pintype "passive"))
      (node (ref "RT") (pin "4") (pinfunction "BYP_4") (pintype "passive"))
    )
    (net (code "72") (name "Net-(STM32A-VCAP_1)") (class "Default")
      (node (ref "C9") (pin "1") (pinfunction "1_1") (pintype "passive"))
      (node (ref "STM32") (pin "31") (pinfunction "VCAP_1_31") (pintype "passive"))
    )
    (net (code "73") (name "Net-(STM32A-VCAP_2)") (class "Default")
      (node (ref "C10") (pin "1") (pinfunction "1_1") (pintype "passive"))
      (node (ref "STM32") (pin "47") (pinfunction "VCAP_2_47") (pintype "passive"))
    )
    (net (code "74") (name "Net-(STM32JB-PA1)") (class "Default")
      (node (ref "R7") (pin "2") (pinfunction "2_2") (pintype "passive"))
      (node (ref "STM32J") (pin "11") (pinfunction "PA1_11") (pintype "passive"))
    )
    (net (code "75") (name "Net-(STM32JB-PA2)") (class "Default")
      (node (ref "R8") (pin "2") (pinfunction "2_2") (pintype "passive"))
      (node (ref "STM32J") (pin "12") (pinfunction "PA2_12") (pintype "passive"))
    )
    (net (code "76") (name "Net-(STM32JB-PA4)") (class "Default")
      (node (ref "R9") (pin "2") (pinfunction "2_2") (pintype "passive"))
      (node (ref "STM32J") (pin "14") (pinfunction "PA4_14") (pintype "passive"))
    )
    (net (code "77") (name "Net-(STM32JB-PA9)") (class "Default")
      (node (ref "R10") (pin "2") (pinfunction "2_2") (pintype "passive"))
      (node (ref "STM32J") (pin "30") (pinfunction "PA9_30") (pintype "passive"))
    )
    (net (code "78") (name "Net-(STM32JB-PA10)") (class "Default")
      (node (ref "R11") (pin "2") (pinfunction "2_2") (pintype "passive"))
      (node (ref "STM32J") (pin "31") (pinfunction "PA10_31") (pintype "passive"))
    )
    (net (code "79") (name "Net-(USB-DM)") (class "Default")
      (node (ref "R14") (pin "2") (pinfunction "2_2") (pintype "passive"))
      (node (ref "USB") (pin "2") (pinfunction "DM_2") (pintype "passive"))
    )
    (net (code "80") (name "Net-(USB-DP)") (class "Default")
      (node (ref "R12") (pin "2") (pinfunction "2_2") (pintype "passive"))
      (node (ref "R15") (pin "2") (pinfunction "2_2") (pintype "passive"))
      (node (ref "USB") (pin "3") (pinfunction "DP_3") (pintype "passive"))
    )
    (net (code "81") (name "Net-(jUSB-DM)") (class "Default")
      (node (ref "R1") (pin "1") (pinfunction "1_1") (pintype "passive"))
      (node (ref "jUSB") (pin "2") (pinfunction "DM_2") (pintype "passive"))
    )
    (net (code "82") (name "Net-(jUSB-DP)") (class "Default")
      (node (ref "R2") (pin "1") (pinfunction "1_1") (pintype "passive"))
      (node (ref "jUSB") (pin "3") (pinfunction "DP_3") (pintype "passive"))
    )
    (net (code "83") (name "VBAT") (class "Default")
      (node (ref "BATIN") (pin "1") (pinfunction "1_1") (pintype "passive"))
      (node (ref "POW") (pin "3") (pinfunction "3_3") (pintype "passive"))
      (node (ref "R19") (pin "1") (pinfunction "1_1") (pintype "passive"))
    )
    (net (code "84") (name "VIN") (class "Default")
      (node (ref "C1") (pin "2") (pinfunction "2_2") (pintype "passive"))
      (node (ref "POW") (pin "2") (pinfunction "2_2") (pintype "passive"))
      (node (ref "RT") (pin "1") (pinfunction "VIN_1") (pintype "passive"))
      (node (ref "RT") (pin "3") (pinfunction "EN_3") (pintype "power_in"))
    )
    (net (code "85") (name "VUSB") (class "Default")
      (node (ref "POW") (pin "1") (pinfunction "1_1") (pintype "passive"))
      (node (ref "R13") (pin "2") (pinfunction "2_2") (pintype "passive"))
      (node (ref "USB") (pin "1") (pinfunction "VBUS_1") (pintype "passive"))
      (node (ref "jUSB") (pin "1") (pinfunction "VBUS_1") (pintype "passive"))
    )
    (net (code "86") (name "unconnected-(DWM-GPIO0{slash}RXOK-Pad15)") (class "Default")
      (node (ref "DWM") (pin "15") (pinfunction "GPIO0/RXOK_15") (pintype "passive"))
    )
    (net (code "87") (name "unconnected-(DWM-GPIO1{slash}SFD-Pad14)") (class "Default")
      (node (ref "DWM") (pin "14") (pinfunction "GPIO1/SFD_14") (pintype "passive"))
    )
    (net (code "88") (name "unconnected-(DWM-GPIO2{slash}RX-Pad13)") (class "Default")
      (node (ref "DWM") (pin "13") (pinfunction "GPIO2/RX_13") (pintype "passive"))
    )
    (net (code "89") (name "unconnected-(DWM-GPIO3{slash}TX-Pad12)") (class "Default")
      (node (ref "DWM") (pin "12") (pinfunction "GPIO3/TX_12") (pintype "passive"))
    )
    (net (code "90") (name "unconnected-(DWM-GPIO4{slash}EXTPA-Pad11)") (class "Default")
      (node (ref "DWM") (pin "11") (pinfunction "GPIO4/EXTPA_11") (pintype "passive"))
    )
    (net (code "91") (name "unconnected-(DWM-GPIO7-Pad4)") (class "Default")
      (node (ref "DWM") (pin "4") (pinfunction "GPIO7_4") (pintype "passive"))
    )
    (net (code "92") (name "unconnected-(KEY-Pad3)") (class "Default")
      (node (ref "KEY") (pin "3") (pinfunction "3_3") (pintype "passive+no_connect"))
    )
    (net (code "93") (name "unconnected-(KEY-Pad4)") (class "Default")
      (node (ref "KEY") (pin "4") (pinfunction "4_4") (pintype "passive+no_connect"))
    )
    (net (code "94") (name "unconnected-(MPU-AUX_CL-Pad7)") (class "Default")
      (node (ref "MPU") (pin "7") (pinfunction "AUX_CL_7") (pintype "passive+no_connect"))
    )
    (net (code "95") (name "unconnected-(MPU-AUX_DA-Pad21)") (class "Default")
      (node (ref "MPU") (pin "21") (pinfunction "AUX_DA_21") (pintype "passive+no_connect"))
    )
    (net (code "96") (name "unconnected-(MPU-NC-Pad2)") (class "Default")
      (node (ref "MPU") (pin "2") (pinfunction "NC_2") (pintype "passive+no_connect"))
    )
    (net (code "97") (name "unconnected-(MPU-NC-Pad3)") (class "Default")
      (node (ref "MPU") (pin "3") (pinfunction "NC_3") (pintype "passive+no_connect"))
    )
    (net (code "98") (name "unconnected-(MPU-NC-Pad4)") (class "Default")
      (node (ref "MPU") (pin "4") (pinfunction "NC_4") (pintype "passive+no_connect"))
    )
    (net (code "99") (name "unconnected-(MPU-NC-Pad5)") (class "Default")
      (node (ref "MPU") (pin "5") (pinfunction "NC_5") (pintype "passive+no_connect"))
    )
    (net (code "100") (name "unconnected-(MPU-NC-Pad6)") (class "Default")
      (node (ref "MPU") (pin "6") (pinfunction "NC_6") (pintype "passive+no_connect"))
    )
    (net (code "101") (name "unconnected-(MPU-NC-Pad14)") (class "Default")
      (node (ref "MPU") (pin "14") (pinfunction "NC_14") (pintype "passive+no_connect"))
    )
    (net (code "102") (name "unconnected-(MPU-NC-Pad15)") (class "Default")
      (node (ref "MPU") (pin "15") (pinfunction "NC_15") (pintype "passive+no_connect"))
    )
    (net (code "103") (name "unconnected-(MPU-NC-Pad16)") (class "Default")
      (node (ref "MPU") (pin "16") (pinfunction "NC_16") (pintype "passive+no_connect"))
    )
    (net (code "104") (name "unconnected-(MPU-NC-Pad17)") (class "Default")
      (node (ref "MPU") (pin "17") (pinfunction "NC_17") (pintype "passive+no_connect"))
    )
    (net (code "105") (name "unconnected-(MPU-RESV-Pad19)") (class "Default")
      (node (ref "MPU") (pin "19") (pinfunction "RESV_19") (pintype "passive+no_connect"))
    )
    (net (code "106") (name "unconnected-(STM32JA-OSC_IN-Pad5)") (class "Default")
      (node (ref "STM32J") (pin "5") (pinfunction "OSC_IN_5") (pintype "passive+no_connect"))
    )
    (net (code "107") (name "unconnected-(STM32JA-OSC_OUT-Pad6)") (class "Default")
      (node (ref "STM32J") (pin "6") (pinfunction "OSC_OUT_6") (pintype "passive+no_connect"))
    )
    (net (code "108") (name "unconnected-(STM32JB-PA3-Pad13)") (class "Default")
      (node (ref "STM32J") (pin "13") (pinfunction "PA3_13") (pintype "passive+no_connect"))
    )
    (net (code "109") (name "unconnected-(STM32JB-PA5-Pad15)") (class "Default")
      (node (ref "STM32J") (pin "15") (pinfunction "PA5_15") (pintype "passive+no_connect"))
    )
    (net (code "110") (name "unconnected-(STM32JB-PA6-Pad16)") (class "Default")
      (node (ref "STM32J") (pin "16") (pinfunction "PA6_16") (pintype "passive+no_connect"))
    )
    (net (code "111") (name "unconnected-(STM32JB-PA7-Pad17)") (class "Default")
      (node (ref "STM32J") (pin "17") (pinfunction "PA7_17") (pintype "passive+no_connect"))
    )
    (net (code "112") (name "unconnected-(STM32JB-PA8-Pad29)") (class "Default")
      (node (ref "STM32J") (pin "29") (pinfunction "PA8_29") (pintype "passive+no_connect"))
    )
    (net (code "113") (name "unconnected-(STM32JB-PA15-Pad38)") (class "Default")
      (node (ref "STM32J") (pin "38") (pinfunction "PA15_38") (pintype "passive+no_connect"))
    )
    (net (code "114") (name "unconnected-(STM32JB-PB0-Pad18)") (class "Default")
      (node (ref "STM32J") (pin "18") (pinfunction "PB0_18") (pintype "passive+no_connect"))
    )
    (net (code "115") (name "unconnected-(STM32JB-PB1-Pad19)") (class "Default")
      (node (ref "STM32J") (pin "19") (pinfunction "PB1_19") (pintype "passive+no_connect"))
    )
    (net (code "116") (name "unconnected-(STM32JB-PB2-Pad20)") (class "Default")
      (node (ref "STM32J") (pin "20") (pinfunction "PB2_20") (pintype "passive+no_connect"))
    )
    (net (code "117") (name "unconnected-(STM32JB-PB3-Pad39)") (class "Default")
      (node (ref "STM32J") (pin "39") (pinfunction "PB3_39") (pintype "passive+no_connect"))
    )
    (net (code "118") (name "unconnected-(STM32JB-PB4-Pad40)") (class "Default")
      (node (ref "STM32J") (pin "40") (pinfunction "PB4_40") (pintype "passive+no_connect"))
    )
    (net (code "119") (name "unconnected-(STM32JB-PB5-Pad41)") (class "Default")
      (node (ref "STM32J") (pin "41") (pinfunction "PB5_41") (pintype "passive+no_connect"))
    )
    (net (code "120") (name "unconnected-(STM32JB-PB6-Pad42)") (class "Default")
      (node (ref "STM32J") (pin "42") (pinfunction "PB6_42") (pintype "passive+no_connect"))
    )
    (net (code "121") (name "unconnected-(STM32JB-PB7-Pad43)") (class "Default")
      (node (ref "STM32J") (pin "43") (pinfunction "PB7_43") (pintype "passive+no_connect"))
    )
    (net (code "122") (name "unconnected-(STM32JB-PB8-Pad45)") (class "Default")
      (node (ref "STM32J") (pin "45") (pinfunction "PB8_45") (pintype "passive+no_connect"))
    )
    (net (code "123") (name "unconnected-(STM32JB-PB9-Pad46)") (class "Default")
      (node (ref "STM32J") (pin "46") (pinfunction "PB9_46") (pintype "passive+no_connect"))
    )
    (net (code "124") (name "unconnected-(STM32JB-PB10-Pad21)") (class "Default")
      (node (ref "STM32J") (pin "21") (pinfunction "PB10_21") (pintype "passive+no_connect"))
    )
    (net (code "125") (name "unconnected-(STM32JB-PB11-Pad22)") (class "Default")
      (node (ref "STM32J") (pin "22") (pinfunction "PB11_22") (pintype "passive+no_connect"))
    )
    (net (code "126") (name "unconnected-(STM32JB-PB12-Pad25)") (class "Default")
      (node (ref "STM32J") (pin "25") (pinfunction "PB12_25") (pintype "passive+no_connect"))
    )
    (net (code "127") (name "unconnected-(STM32JB-PB13-Pad26)") (class "Default")
      (node (ref "STM32J") (pin "26") (pinfunction "PB13_26") (pintype "passive+no_connect"))
    )
    (net (code "128") (name "unconnected-(STM32JB-PB14-Pad27)") (class "Default")
      (node (ref "STM32J") (pin "27") (pinfunction "PB14_27") (pintype "passive+no_connect"))
    )
    (net (code "129") (name "unconnected-(STM32JB-PB15-Pad28)") (class "Default")
      (node (ref "STM32J") (pin "28") (pinfunction "PB15_28") (pintype "passive+no_connect"))
    )
    (net (code "130") (name "unconnected-(STM32JB-PC13-Pad2)") (class "Default")
      (node (ref "STM32J") (pin "2") (pinfunction "PC13_2") (pintype "passive+no_connect"))
    )
    (net (code "131") (name "unconnected-(STM32JB-PC14-Pad3)") (class "Default")
      (node (ref "STM32J") (pin "3") (pinfunction "PC14_3") (pintype "passive+no_connect"))
    )
    (net (code "132") (name "unconnected-(STM32JB-PC15-Pad4)") (class "Default")
      (node (ref "STM32J") (pin "4") (pinfunction "PC15_4") (pintype "passive+no_connect"))
    )
    (net (code "133") (name "unconnected-(jUSB-ID-Pad4)") (class "Default")
      (node (ref "jUSB") (pin "4") (pinfunction "ID_4") (pintype "passive+no_connect"))
    )
  )
)
